# LeatherSynth.net
KiCad netlist of a schematic drawn in EAGLE
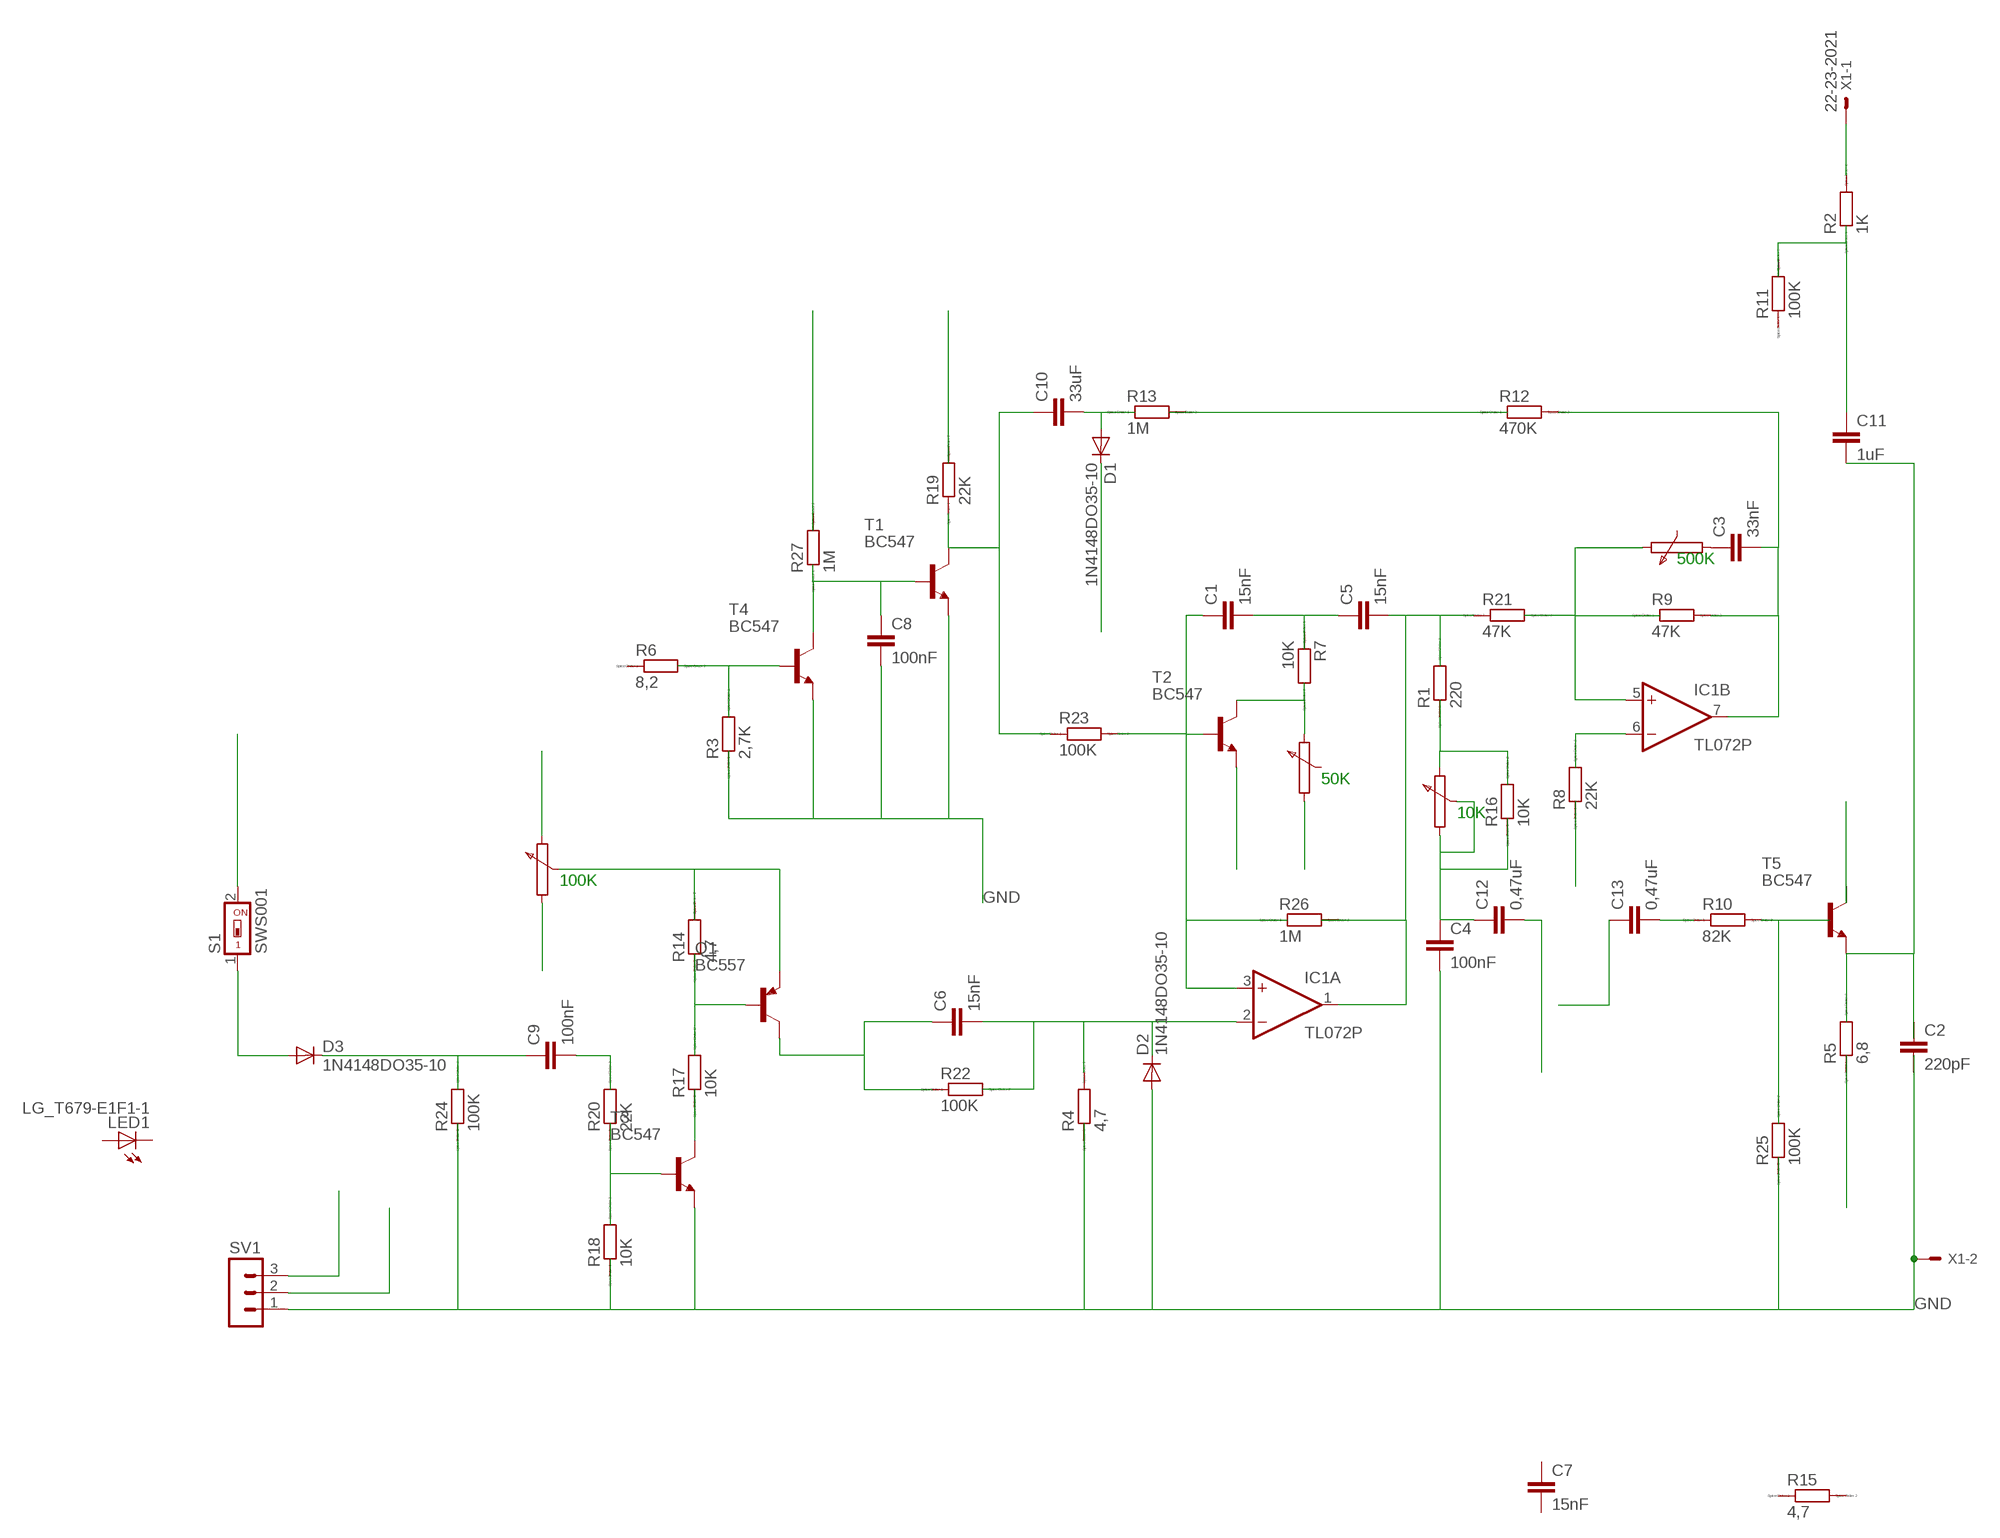
[diagram p0: schematic, sheet 1]

(export (version "E")
  (design (tool "Eeschema 10.0.6"))
  (components
    (comp (ref "C1")
      (value "15nF")
      (footprint "eagle-import:C2220K")
      (libsource (lib "eagle-import") (part "C-EUC2220K"))
    )
    (comp (ref "C2")
      (value "220pF")
      (footprint "eagle-import:C2220K")
      (libsource (lib "eagle-import") (part "C-EUC2220K"))
    )
    (comp (ref "C3")
      (value "33nF")
      (footprint "eagle-import:C2220K")
      (libsource (lib "eagle-import") (part "C-EUC2220K"))
    )
    (comp (ref "C4")
      (value "100nF")
      (footprint "eagle-import:C2220K")
      (libsource (lib "eagle-import") (part "C-EUC2220K"))
    )
    (comp (ref "C5")
      (value "15nF")
      (footprint "eagle-import:C2220K")
      (libsource (lib "eagle-import") (part "C-EUC2220K"))
    )
    (comp (ref "C6")
      (value "15nF")
      (footprint "eagle-import:C2220K")
      (libsource (lib "eagle-import") (part "C-EUC2220K"))
    )
    (comp (ref "C7")
      (value "15nF")
      (footprint "eagle-import:C2220K")
      (libsource (lib "eagle-import") (part "C-EUC2220K"))
    )
    (comp (ref "C8")
      (value "100nF")
      (footprint "eagle-import:C2220K")
      (libsource (lib "eagle-import") (part "C-EUC2220K"))
    )
    (comp (ref "C9")
      (value "100nF")
      (footprint "eagle-import:C2220K")
      (libsource (lib "eagle-import") (part "C-EUC2220K"))
    )
    (comp (ref "C10")
      (value "33uF")
      (footprint "eagle-import:C2220K")
      (libsource (lib "eagle-import") (part "C-EUC2220K"))
    )
    (comp (ref "C11")
      (value "1uF")
      (footprint "eagle-import:C2220K")
      (libsource (lib "eagle-import") (part "C-EUC2220K"))
    )
    (comp (ref "C12")
      (value "0,47uF")
      (footprint "eagle-import:C2220K")
      (libsource (lib "eagle-import") (part "C-EUC2220K"))
    )
    (comp (ref "C13")
      (value "0,47uF")
      (footprint "eagle-import:C2220K")
      (libsource (lib "eagle-import") (part "C-EUC2220K"))
    )
    (comp (ref "D1")
      (value "1N4148DO35-10")
      (footprint "eagle-import:DO35-10")
      (libsource (lib "eagle-import") (part "1N4148DO35-10"))
    )
    (comp (ref "D2")
      (value "1N4148DO35-10")
      (footprint "eagle-import:DO35-10")
      (libsource (lib "eagle-import") (part "1N4148DO35-10"))
    )
    (comp (ref "D3")
      (value "1N4148DO35-10")
      (footprint "eagle-import:DO35-10")
      (libsource (lib "eagle-import") (part "1N4148DO35-10"))
    )
    (comp (ref "IC1")
      (value "TL072P")
      (footprint "eagle-import:DIL08")
      (libsource (lib "eagle-import") (part "TL072P"))
    )
    (comp (ref "LED1")
      (value "LG_T679-E1F1-1")
      (footprint "eagle-import:PLCC2")
      (libsource (lib "eagle-import") (part "_T679-?-1E1F1LG"))
    )
    (comp (ref "Q1")
      (value "BC557")
      (footprint "eagle-import:TO92")
      (libsource (lib "eagle-import") (part "BC557"))
    )
    (comp (ref "R1")
      (value "220")
      (footprint "eagle-import:R2010")
      (libsource (lib "eagle-import") (part "RR2010"))
    )
    (comp (ref "R2")
      (value "1K")
      (footprint "eagle-import:R2010")
      (libsource (lib "eagle-import") (part "RR2010"))
    )
    (comp (ref "R3")
      (value "2,7K")
      (footprint "eagle-import:R2010")
      (libsource (lib "eagle-import") (part "RR2010"))
    )
    (comp (ref "R4")
      (value "4,7")
      (footprint "eagle-import:R2010")
      (libsource (lib "eagle-import") (part "RR2010"))
    )
    (comp (ref "R5")
      (value "6,8")
      (footprint "eagle-import:R2010")
      (libsource (lib "eagle-import") (part "RR2010"))
    )
    (comp (ref "R6")
      (value "8,2")
      (footprint "eagle-import:R2010")
      (libsource (lib "eagle-import") (part "RR2010"))
    )
    (comp (ref "R7")
      (value "10K")
      (footprint "eagle-import:R2010")
      (libsource (lib "eagle-import") (part "RR2010"))
    )
    (comp (ref "R8")
      (value "22K")
      (footprint "eagle-import:R2010")
      (libsource (lib "eagle-import") (part "RR2010"))
    )
    (comp (ref "R9")
      (value "47K")
      (footprint "eagle-import:R2010")
      (libsource (lib "eagle-import") (part "RR2010"))
    )
    (comp (ref "R10")
      (value "82K")
      (footprint "eagle-import:R2010")
      (libsource (lib "eagle-import") (part "RR2010"))
    )
    (comp (ref "R11")
      (value "100K")
      (footprint "eagle-import:R2010")
      (libsource (lib "eagle-import") (part "RR2010"))
    )
    (comp (ref "R12")
      (value "470K")
      (footprint "eagle-import:R2010")
      (libsource (lib "eagle-import") (part "RR2010"))
    )
    (comp (ref "R13")
      (value "1M")
      (footprint "eagle-import:R2010")
      (libsource (lib "eagle-import") (part "RR2010"))
    )
    (comp (ref "R14")
      (value "4,7")
      (footprint "eagle-import:R2010")
      (libsource (lib "eagle-import") (part "RR2010"))
    )
    (comp (ref "R15")
      (value "4,7")
      (footprint "eagle-import:R2010")
      (libsource (lib "eagle-import") (part "RR2010"))
    )
    (comp (ref "R16")
      (value "10K")
      (footprint "eagle-import:R2010")
      (libsource (lib "eagle-import") (part "RR2010"))
    )
    (comp (ref "R17")
      (value "10K")
      (footprint "eagle-import:R2010")
      (libsource (lib "eagle-import") (part "RR2010"))
    )
    (comp (ref "R18")
      (value "10K")
      (footprint "eagle-import:R2010")
      (libsource (lib "eagle-import") (part "RR2010"))
    )
    (comp (ref "R19")
      (value "22K")
      (footprint "eagle-import:R2010")
      (libsource (lib "eagle-import") (part "RR2010"))
    )
    (comp (ref "R20")
      (value "22K")
      (footprint "eagle-import:R2010")
      (libsource (lib "eagle-import") (part "RR2010"))
    )
    (comp (ref "R21")
      (value "47K")
      (footprint "eagle-import:R2010")
      (libsource (lib "eagle-import") (part "RR2010"))
    )
    (comp (ref "R22")
      (value "100K")
      (footprint "eagle-import:R2010")
      (libsource (lib "eagle-import") (part "RR2010"))
    )
    (comp (ref "R23")
      (value "100K")
      (footprint "eagle-import:R2010")
      (libsource (lib "eagle-import") (part "RR2010"))
    )
    (comp (ref "R24")
      (value "100K")
      (footprint "eagle-import:R2010")
      (libsource (lib "eagle-import") (part "RR2010"))
    )
    (comp (ref "R25")
      (value "100K")
      (footprint "eagle-import:R2010")
      (libsource (lib "eagle-import") (part "RR2010"))
    )
    (comp (ref "R26")
      (value "1M")
      (footprint "eagle-import:R2010")
      (libsource (lib "eagle-import") (part "RR2010"))
    )
    (comp (ref "R27")
      (value "1M")
      (footprint "eagle-import:R2010")
      (libsource (lib "eagle-import") (part "RR2010"))
    )
    (comp (ref "S1")
      (value "SWS001")
      (footprint "eagle-import:SMS-001")
      (libsource (lib "eagle-import") (part "SWS001"))
    )
    (comp (ref "SV1")
      (value "MA03-1")
      (footprint "eagle-import:MA03-1")
      (libsource (lib "eagle-import") (part "MA03-1"))
    )
    (comp (ref "T1")
      (value "BC547")
      (footprint "eagle-import:TO92")
      (libsource (lib "eagle-import") (part "BC547"))
    )
    (comp (ref "T2")
      (value "BC547")
      (footprint "eagle-import:TO92")
      (libsource (lib "eagle-import") (part "BC547"))
    )
    (comp (ref "T3")
      (value "BC547")
      (footprint "eagle-import:TO92")
      (libsource (lib "eagle-import") (part "BC547"))
    )
    (comp (ref "T4")
      (value "BC547")
      (footprint "eagle-import:TO92")
      (libsource (lib "eagle-import") (part "BC547"))
    )
    (comp (ref "T5")
      (value "BC547")
      (footprint "eagle-import:TO92")
      (libsource (lib "eagle-import") (part "BC547"))
    )
    (comp (ref "X1")
      (value "22-23-2021")
      (footprint "eagle-import:22-23-2021")
      (fields (field (name "MF") "MOLEX"))
      (libsource (lib "eagle-import") (part "22-23-2021"))
    )
  )
  (nets
    (net (code "1") (name "/GND") (class "Default")
      (node (ref "C4") (pin "2") (pinfunction "2_2") (pintype "passive"))
      (node (ref "C8") (pin "2") (pinfunction "2_2") (pintype "passive"))
      (node (ref "D2") (pin "A") (pinfunction "A_A") (pintype "passive"))
      (node (ref "SV1") (pin "1") (pinfunction "1_1") (pintype "passive"))
      (node (ref "T1") (pin "1") (pinfunction "E_1") (pintype "passive"))
      (node (ref "T3") (pin "1") (pinfunction "E_1") (pintype "passive"))
      (node (ref "T4") (pin "1") (pinfunction "E_1") (pintype "passive"))
      (node (ref "X1") (pin "2") (pinfunction "S_2") (pintype "passive"))
    )
    (net (code "2") (name "Net-(C1-Pad2)") (class "Default")
      (node (ref "C1") (pin "2") (pinfunction "2_2") (pintype "passive"))
      (node (ref "C5") (pin "1") (pinfunction "1_1") (pintype "passive"))
    )
    (net (code "3") (name "Net-(C9-Pad1)") (class "Default")
      (node (ref "C9") (pin "1") (pinfunction "1_1") (pintype "passive"))
      (node (ref "D3") (pin "C") (pinfunction "C_C") (pintype "passive"))
    )
    (net (code "4") (name "Net-(C10-Pad2)") (class "Default")
      (node (ref "C10") (pin "2") (pinfunction "2_2") (pintype "passive"))
      (node (ref "D1") (pin "A") (pinfunction "A_A") (pintype "passive"))
    )
    (net (code "5") (name "Net-(C11-Pad1)") (class "Default")
      (node (ref "C11") (pin "1") (pinfunction "1_1") (pintype "passive"))
      (node (ref "R2") (pin "1") (pinfunction "1_1") (pintype "passive"))
    )
    (net (code "6") (name "Net-(C12-Pad1)") (class "Default")
      (node (ref "C12") (pin "1") (pinfunction "1_1") (pintype "passive"))
      (node (ref "C4") (pin "1") (pinfunction "1_1") (pintype "passive"))
    )
    (net (code "7") (name "Net-(C13-Pad2)") (class "Default")
      (node (ref "C13") (pin "2") (pinfunction "2_2") (pintype "passive"))
      (node (ref "R10") (pin "1") (pinfunction "1_1") (pintype "passive"))
    )
    (net (code "8") (name "Net-(D3-PadA)") (class "Default")
      (node (ref "D3") (pin "A") (pinfunction "A_A") (pintype "passive"))
      (node (ref "S1") (pin "1") (pinfunction "1_1") (pintype "passive"))
    )
    (net (code "9") (name "Net-(IC1A-+IN)") (class "Default")
      (node (ref "C1") (pin "1") (pinfunction "1_1") (pintype "passive"))
      (node (ref "IC1") (pin "3") (pinfunction "+IN_3") (pintype "input"))
      (node (ref "R23") (pin "2") (pinfunction "2_2") (pintype "passive"))
      (node (ref "T2") (pin "2") (pinfunction "B_2") (pintype "passive"))
    )
    (net (code "10") (name "Net-(IC1A--IN)") (class "Default")
      (node (ref "C6") (pin "2") (pinfunction "2_2") (pintype "passive"))
      (node (ref "D2") (pin "C") (pinfunction "C_C") (pintype "passive"))
      (node (ref "IC1") (pin "2") (pinfunction "-IN_2") (pintype "input"))
      (node (ref "R4") (pin "2") (pinfunction "2_2") (pintype "passive"))
    )
    (net (code "11") (name "Net-(IC1A-OUT)") (class "Default")
      (node (ref "C5") (pin "2") (pinfunction "2_2") (pintype "passive"))
      (node (ref "IC1") (pin "1") (pinfunction "OUT_1") (pintype "output"))
      (node (ref "R21") (pin "1") (pinfunction "1_1") (pintype "passive"))
    )
    (net (code "12") (name "Net-(IC1B-OUT)") (class "Default")
      (node (ref "C3") (pin "2") (pinfunction "2_2") (pintype "passive"))
      (node (ref "IC1") (pin "7") (pinfunction "OUT_7") (pintype "output"))
      (node (ref "R12") (pin "2") (pinfunction "2_2") (pintype "passive"))
      (node (ref "R9") (pin "2") (pinfunction "2_2") (pintype "passive"))
    )
    (net (code "13") (name "Net-(Q1-C)") (class "Default")
      (node (ref "C6") (pin "1") (pinfunction "1_1") (pintype "passive"))
      (node (ref "Q1") (pin "3") (pinfunction "C_3") (pintype "passive"))
      (node (ref "R22") (pin "1") (pinfunction "1_1") (pintype "passive"))
    )
    (net (code "14") (name "Net-(T1-B)") (class "Default")
      (node (ref "C8") (pin "1") (pinfunction "1_1") (pintype "passive"))
      (node (ref "R27") (pin "1") (pinfunction "1_1") (pintype "passive"))
      (node (ref "T1") (pin "2") (pinfunction "B_2") (pintype "passive"))
      (node (ref "T4") (pin "3") (pinfunction "C_3") (pintype "passive"))
    )
    (net (code "15") (name "Net-(T1-C)") (class "Default")
      (node (ref "C10") (pin "1") (pinfunction "1_1") (pintype "passive"))
      (node (ref "R19") (pin "1") (pinfunction "1_1") (pintype "passive"))
      (node (ref "R23") (pin "1") (pinfunction "1_1") (pintype "passive"))
      (node (ref "T1") (pin "3") (pinfunction "C_3") (pintype "passive"))
    )
    (net (code "16") (name "Net-(T2-C)") (class "Default")
      (node (ref "R7") (pin "2") (pinfunction "2_2") (pintype "passive"))
      (node (ref "T2") (pin "3") (pinfunction "C_3") (pintype "passive"))
    )
    (net (code "17") (name "Net-(T5-E)") (class "Default")
      (node (ref "C11") (pin "2") (pinfunction "2_2") (pintype "passive"))
      (node (ref "T5") (pin "1") (pinfunction "E_1") (pintype "passive"))
    )
    (net (code "18") (name "Net-(X1A-S)") (class "Default")
      (node (ref "R2") (pin "2") (pinfunction "2_2") (pintype "passive"))
      (node (ref "X1") (pin "1") (pinfunction "S_1") (pintype "passive"))
    )
    (net (code "19") (name "unconnected-(C2-Pad1)") (class "Default")
      (node (ref "C2") (pin "1") (pinfunction "1_1") (pintype "passive"))
    )
    (net (code "20") (name "unconnected-(C2-Pad2)") (class "Default")
      (node (ref "C2") (pin "2") (pinfunction "2_2") (pintype "passive"))
    )
    (net (code "21") (name "unconnected-(C3-Pad1)") (class "Default")
      (node (ref "C3") (pin "1") (pinfunction "1_1") (pintype "passive"))
    )
    (net (code "22") (name "unconnected-(C7-Pad1)") (class "Default")
      (node (ref "C7") (pin "1") (pinfunction "1_1") (pintype "passive"))
    )
    (net (code "23") (name "unconnected-(C7-Pad2)") (class "Default")
      (node (ref "C7") (pin "2") (pinfunction "2_2") (pintype "passive"))
    )
    (net (code "24") (name "unconnected-(C9-Pad2)") (class "Default")
      (node (ref "C9") (pin "2") (pinfunction "2_2") (pintype "passive"))
    )
    (net (code "25") (name "unconnected-(C12-Pad2)") (class "Default")
      (node (ref "C12") (pin "2") (pinfunction "2_2") (pintype "passive"))
    )
    (net (code "26") (name "unconnected-(C13-Pad1)") (class "Default")
      (node (ref "C13") (pin "1") (pinfunction "1_1") (pintype "passive"))
    )
    (net (code "27") (name "unconnected-(D1-PadC)") (class "Default")
      (node (ref "D1") (pin "C") (pinfunction "C_C") (pintype "passive"))
    )
    (net (code "28") (name "unconnected-(IC1B-+IN-Pad5)") (class "Default")
      (node (ref "IC1") (pin "5") (pinfunction "+IN_5") (pintype "input"))
    )
    (net (code "29") (name "unconnected-(IC1B--IN-Pad6)") (class "Default")
      (node (ref "IC1") (pin "6") (pinfunction "-IN_6") (pintype "input"))
    )
    (net (code "30") (name "unconnected-(LED1-PadA)") (class "Default")
      (node (ref "LED1") (pin "A") (pinfunction "A_A") (pintype "passive"))
    )
    (net (code "31") (name "unconnected-(LED1-PadC)") (class "Default")
      (node (ref "LED1") (pin "C") (pinfunction "C_C") (pintype "passive"))
    )
    (net (code "32") (name "unconnected-(Q1-B-Pad2)") (class "Default")
      (node (ref "Q1") (pin "2") (pinfunction "B_2") (pintype "passive"))
    )
    (net (code "33") (name "unconnected-(Q1-E-Pad1)") (class "Default")
      (node (ref "Q1") (pin "1") (pinfunction "E_1") (pintype "passive"))
    )
    (net (code "34") (name "unconnected-(R1-Pad1)") (class "Default")
      (node (ref "R1") (pin "1") (pinfunction "1_1") (pintype "passive"))
    )
    (net (code "35") (name "unconnected-(R1-Pad2)") (class "Default")
      (node (ref "R1") (pin "2") (pinfunction "2_2") (pintype "passive"))
    )
    (net (code "36") (name "unconnected-(R3-Pad1)") (class "Default")
      (node (ref "R3") (pin "1") (pinfunction "1_1") (pintype "passive"))
    )
    (net (code "37") (name "unconnected-(R3-Pad2)") (class "Default")
      (node (ref "R3") (pin "2") (pinfunction "2_2") (pintype "passive"))
    )
    (net (code "38") (name "unconnected-(R4-Pad1)") (class "Default")
      (node (ref "R4") (pin "1") (pinfunction "1_1") (pintype "passive"))
    )
    (net (code "39") (name "unconnected-(R5-Pad1)") (class "Default")
      (node (ref "R5") (pin "1") (pinfunction "1_1") (pintype "passive"))
    )
    (net (code "40") (name "unconnected-(R5-Pad2)") (class "Default")
      (node (ref "R5") (pin "2") (pinfunction "2_2") (pintype "passive"))
    )
    (net (code "41") (name "unconnected-(R6-Pad1)") (class "Default")
      (node (ref "R6") (pin "1") (pinfunction "1_1") (pintype "passive"))
    )
    (net (code "42") (name "unconnected-(R6-Pad2)") (class "Default")
      (node (ref "R6") (pin "2") (pinfunction "2_2") (pintype "passive"))
    )
    (net (code "43") (name "unconnected-(R7-Pad1)") (class "Default")
      (node (ref "R7") (pin "1") (pinfunction "1_1") (pintype "passive"))
    )
    (net (code "44") (name "unconnected-(R8-Pad1)") (class "Default")
      (node (ref "R8") (pin "1") (pinfunction "1_1") (pintype "passive"))
    )
    (net (code "45") (name "unconnected-(R8-Pad2)") (class "Default")
      (node (ref "R8") (pin "2") (pinfunction "2_2") (pintype "passive"))
    )
    (net (code "46") (name "unconnected-(R9-Pad1)") (class "Default")
      (node (ref "R9") (pin "1") (pinfunction "1_1") (pintype "passive"))
    )
    (net (code "47") (name "unconnected-(R10-Pad2)") (class "Default")
      (node (ref "R10") (pin "2") (pinfunction "2_2") (pintype "passive"))
    )
    (net (code "48") (name "unconnected-(R11-Pad1)") (class "Default")
      (node (ref "R11") (pin "1") (pinfunction "1_1") (pintype "passive"))
    )
    (net (code "49") (name "unconnected-(R11-Pad2)") (class "Default")
      (node (ref "R11") (pin "2") (pinfunction "2_2") (pintype "passive"))
    )
    (net (code "50") (name "unconnected-(R12-Pad1)") (class "Default")
      (node (ref "R12") (pin "1") (pinfunction "1_1") (pintype "passive"))
    )
    (net (code "51") (name "unconnected-(R13-Pad1)") (class "Default")
      (node (ref "R13") (pin "1") (pinfunction "1_1") (pintype "passive"))
    )
    (net (code "52") (name "unconnected-(R13-Pad2)") (class "Default")
      (node (ref "R13") (pin "2") (pinfunction "2_2") (pintype "passive"))
    )
    (net (code "53") (name "unconnected-(R14-Pad1)") (class "Default")
      (node (ref "R14") (pin "1") (pinfunction "1_1") (pintype "passive"))
    )
    (net (code "54") (name "unconnected-(R14-Pad2)") (class "Default")
      (node (ref "R14") (pin "2") (pinfunction "2_2") (pintype "passive"))
    )
    (net (code "55") (name "unconnected-(R15-Pad1)") (class "Default")
      (node (ref "R15") (pin "1") (pinfunction "1_1") (pintype "passive"))
    )
    (net (code "56") (name "unconnected-(R15-Pad2)") (class "Default")
      (node (ref "R15") (pin "2") (pinfunction "2_2") (pintype "passive"))
    )
    (net (code "57") (name "unconnected-(R16-Pad1)") (class "Default")
      (node (ref "R16") (pin "1") (pinfunction "1_1") (pintype "passive"))
    )
    (net (code "58") (name "unconnected-(R16-Pad2)") (class "Default")
      (node (ref "R16") (pin "2") (pinfunction "2_2") (pintype "passive"))
    )
    (net (code "59") (name "unconnected-(R17-Pad1)") (class "Default")
      (node (ref "R17") (pin "1") (pinfunction "1_1") (pintype "passive"))
    )
    (net (code "60") (name "unconnected-(R17-Pad2)") (class "Default")
      (node (ref "R17") (pin "2") (pinfunction "2_2") (pintype "passive"))
    )
    (net (code "61") (name "unconnected-(R18-Pad1)") (class "Default")
      (node (ref "R18") (pin "1") (pinfunction "1_1") (pintype "passive"))
    )
    (net (code "62") (name "unconnected-(R18-Pad2)") (class "Default")
      (node (ref "R18") (pin "2") (pinfunction "2_2") (pintype "passive"))
    )
    (net (code "63") (name "unconnected-(R19-Pad2)") (class "Default")
      (node (ref "R19") (pin "2") (pinfunction "2_2") (pintype "passive"))
    )
    (net (code "64") (name "unconnected-(R20-Pad1)") (class "Default")
      (node (ref "R20") (pin "1") (pinfunction "1_1") (pintype "passive"))
    )
    (net (code "65") (name "unconnected-(R20-Pad2)") (class "Default")
      (node (ref "R20") (pin "2") (pinfunction "2_2") (pintype "passive"))
    )
    (net (code "66") (name "unconnected-(R21-Pad2)") (class "Default")
      (node (ref "R21") (pin "2") (pinfunction "2_2") (pintype "passive"))
    )
    (net (code "67") (name "unconnected-(R22-Pad2)") (class "Default")
      (node (ref "R22") (pin "2") (pinfunction "2_2") (pintype "passive"))
    )
    (net (code "68") (name "unconnected-(R24-Pad1)") (class "Default")
      (node (ref "R24") (pin "1") (pinfunction "1_1") (pintype "passive"))
    )
    (net (code "69") (name "unconnected-(R24-Pad2)") (class "Default")
      (node (ref "R24") (pin "2") (pinfunction "2_2") (pintype "passive"))
    )
    (net (code "70") (name "unconnected-(R25-Pad1)") (class "Default")
      (node (ref "R25") (pin "1") (pinfunction "1_1") (pintype "passive"))
    )
    (net (code "71") (name "unconnected-(R25-Pad2)") (class "Default")
      (node (ref "R25") (pin "2") (pinfunction "2_2") (pintype "passive"))
    )
    (net (code "72") (name "unconnected-(R26-Pad1)") (class "Default")
      (node (ref "R26") (pin "1") (pinfunction "1_1") (pintype "passive"))
    )
    (net (code "73") (name "unconnected-(R26-Pad2)") (class "Default")
      (node (ref "R26") (pin "2") (pinfunction "2_2") (pintype "passive"))
    )
    (net (code "74") (name "unconnected-(R27-Pad2)") (class "Default")
      (node (ref "R27") (pin "2") (pinfunction "2_2") (pintype "passive"))
    )
    (net (code "75") (name "unconnected-(S1-Pad2)") (class "Default")
      (node (ref "S1") (pin "2") (pinfunction "2_2") (pintype "passive"))
    )
    (net (code "76") (name "unconnected-(SV1-Pad2)") (class "Default")
      (node (ref "SV1") (pin "2") (pinfunction "2_2") (pintype "passive"))
    )
    (net (code "77") (name "unconnected-(SV1-Pad3)") (class "Default")
      (node (ref "SV1") (pin "3") (pinfunction "3_3") (pintype "passive"))
    )
    (net (code "78") (name "unconnected-(T2-E-Pad1)") (class "Default")
      (node (ref "T2") (pin "1") (pinfunction "E_1") (pintype "passive"))
    )
    (net (code "79") (name "unconnected-(T3-B-Pad2)") (class "Default")
      (node (ref "T3") (pin "2") (pinfunction "B_2") (pintype "passive"))
    )
    (net (code "80") (name "unconnected-(T3-C-Pad3)") (class "Default")
      (node (ref "T3") (pin "3") (pinfunction "C_3") (pintype "passive"))
    )
    (net (code "81") (name "unconnected-(T4-B-Pad2)") (class "Default")
      (node (ref "T4") (pin "2") (pinfunction "B_2") (pintype "passive"))
    )
    (net (code "82") (name "unconnected-(T5-B-Pad2)") (class "Default")
      (node (ref "T5") (pin "2") (pinfunction "B_2") (pintype "passive"))
    )
    (net (code "83") (name "unconnected-(T5-C-Pad3)") (class "Default")
      (node (ref "T5") (pin "3") (pinfunction "C_3") (pintype "passive"))
    )
  )
)
